# fCPU.net
KiCad netlist of a schematic drawn in EAGLE
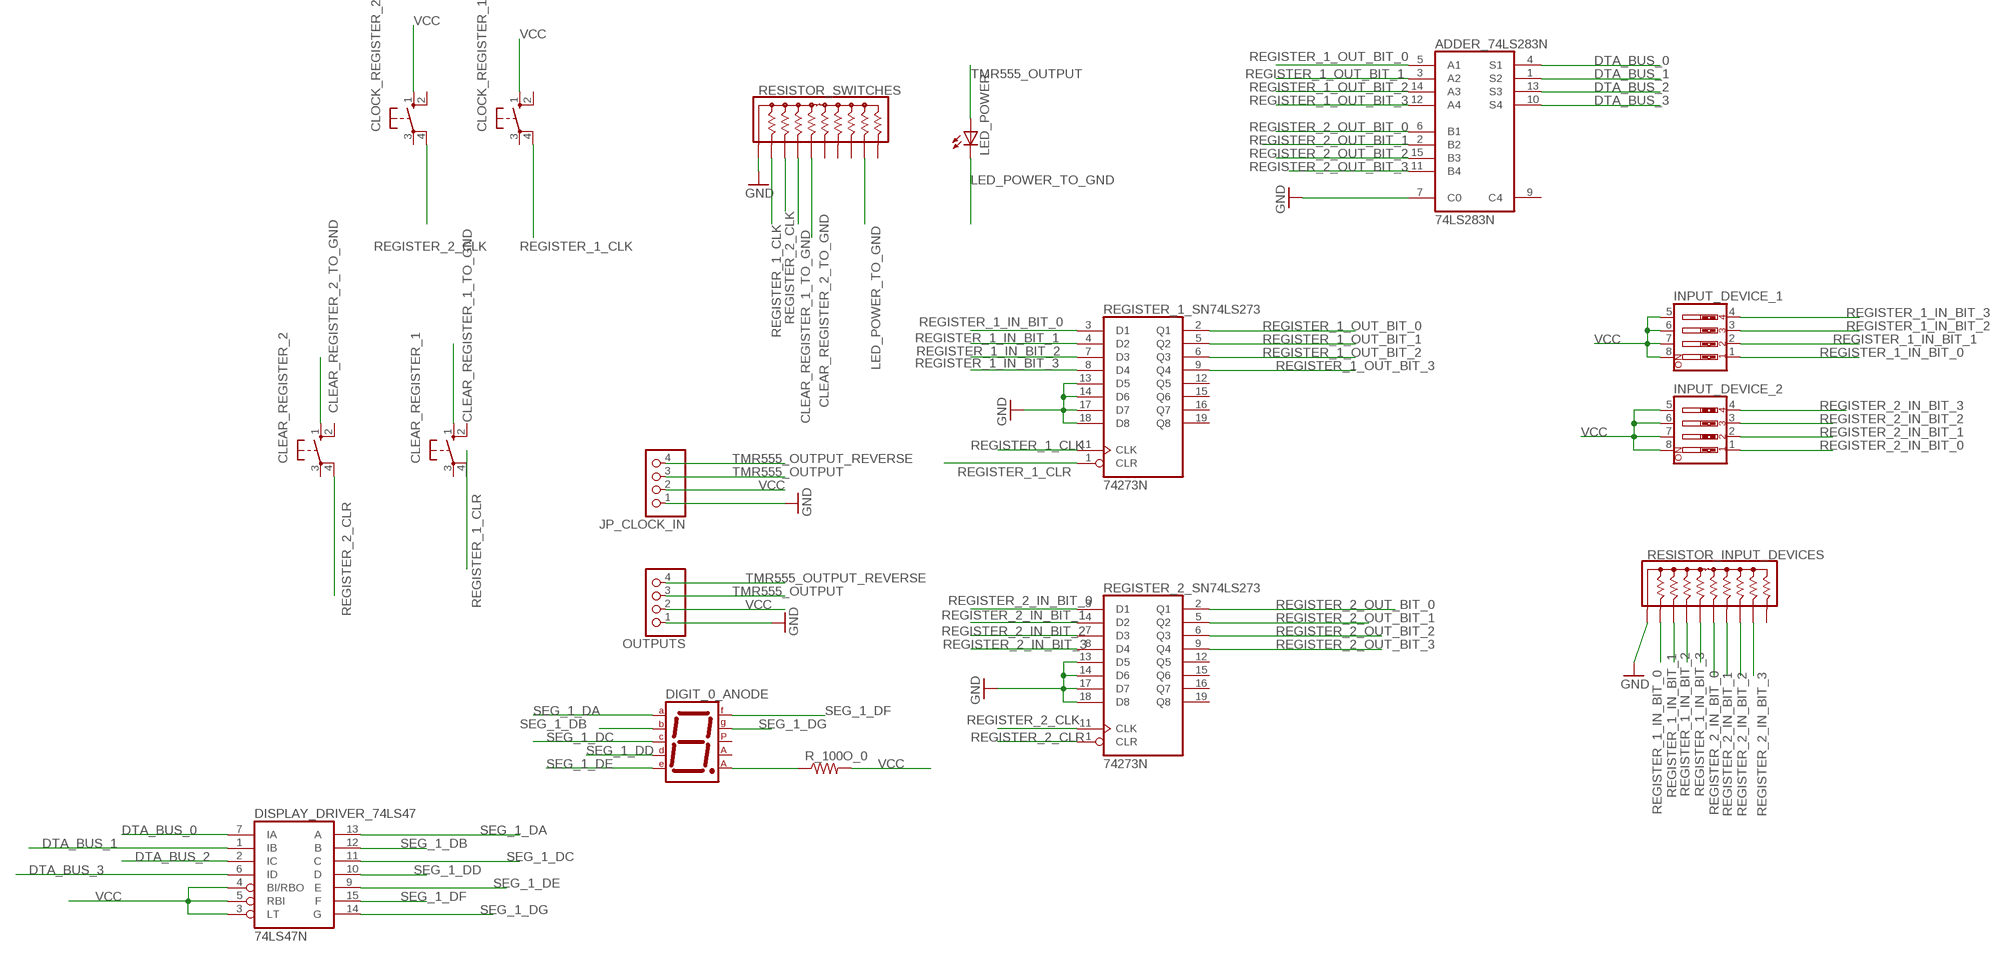
[diagram p0: schematic, sheet 1]

(export (version "E")
  (design (tool "Eeschema 10.0.6"))
  (components
    (comp (ref "ADDER_74LS283N")
      (value "74LS283N")
      (footprint "eagle-import:DIL16")
      (libsource (lib "eagle-import") (part "74283NLS"))
    )
    (comp (ref "CLEAR_REGISTER_1")
      (value "10-XX")
      (footprint "eagle-import:B3F-10XX")
      (fields (field (name "MPN") "B3F-1000"))
      (libsource (lib "eagle-import") (part "10-XX"))
    )
    (comp (ref "CLEAR_REGISTER_2")
      (value "10-XX")
      (footprint "eagle-import:B3F-10XX")
      (fields (field (name "MPN") "B3F-1000"))
      (libsource (lib "eagle-import") (part "10-XX"))
    )
    (comp (ref "CLOCK_REGISTER_1")
      (value "10-XX")
      (footprint "eagle-import:B3F-10XX")
      (fields (field (name "MPN") "B3F-1000"))
      (libsource (lib "eagle-import") (part "10-XX"))
    )
    (comp (ref "CLOCK_REGISTER_2")
      (value "10-XX")
      (footprint "eagle-import:B3F-10XX")
      (fields (field (name "MPN") "B3F-1000"))
      (libsource (lib "eagle-import") (part "10-XX"))
    )
    (comp (ref "DIGIT_0_ANODE")
      (value "7SEG-CA")
      (footprint "eagle-import:7SEG-13")
      (libsource (lib "eagle-import") (part "7SEG-CA"))
    )
    (comp (ref "DISPLAY_DRIVER_74LS47")
      (value "74LS47N")
      (footprint "eagle-import:DIL16")
      (libsource (lib "eagle-import") (part "7447NLS"))
    )
    (comp (ref "INPUT_DEVICE_1")
      (value "SW_DIP-4")
      (footprint "eagle-import:EDG-04")
      (libsource (lib "eagle-import") (part "SW_DIP-4"))
    )
    (comp (ref "INPUT_DEVICE_2")
      (value "SW_DIP-4")
      (footprint "eagle-import:EDG-04")
      (libsource (lib "eagle-import") (part "SW_DIP-4"))
    )
    (comp (ref "JP_CLOCK_IN")
      (value "PINHD-1X4")
      (footprint "eagle-import:1X04")
      (libsource (lib "eagle-import") (part "PINHD-1X4"))
    )
    (comp (ref "LED_POWER")
      (value "LEDSMT1206")
      (footprint "eagle-import:1206")
      (libsource (lib "eagle-import") (part "LEDSMT1206"))
    )
    (comp (ref "OUTPUTS")
      (value "PINHD-1X4")
      (footprint "eagle-import:1X04")
      (libsource (lib "eagle-import") (part "PINHD-1X4"))
    )
    (comp (ref "REGISTER_1_SN74LS273")
      (value "74273N")
      (footprint "eagle-import:DIL20")
      (libsource (lib "eagle-import") (part "74273N"))
    )
    (comp (ref "REGISTER_2_SN74LS273")
      (value "74273N")
      (footprint "eagle-import:DIL20")
      (libsource (lib "eagle-import") (part "74273N"))
    )
    (comp (ref "RESISTOR_INPUT_DEVICES")
      (value "4610X")
      (footprint "eagle-import:SIP10")
      (libsource (lib "eagle-import") (part "4610X"))
    )
    (comp (ref "RESISTOR_SWITCHES")
      (value "4610X")
      (footprint "eagle-import:SIP10")
      (libsource (lib "eagle-import") (part "4610X"))
    )
    (comp (ref "R_100O_0")
      (value "R-US_R1206")
      (footprint "eagle-import:R1206")
      (libsource (lib "eagle-import") (part "R-US_R1206"))
    )
  )
  (nets
    (net (code "1") (name "/CLEAR_REGISTER_1_TO_GND") (class "Default")
      (node (ref "CLEAR_REGISTER_1") (pin "1") (pinfunction "S_1") (pintype "passive"))
      (node (ref "RESISTOR_SWITCHES") (pin "4") (pinfunction "4_4") (pintype "passive"))
    )
    (net (code "2") (name "/CLEAR_REGISTER_2_TO_GND") (class "Default")
      (node (ref "CLEAR_REGISTER_2") (pin "1") (pinfunction "S_1") (pintype "passive"))
      (node (ref "RESISTOR_SWITCHES") (pin "5") (pinfunction "5_5") (pintype "passive"))
    )
    (net (code "3") (name "/DTA_BUS_0") (class "Default")
      (node (ref "ADDER_74LS283N") (pin "4") (pinfunction "S1_4") (pintype "output"))
      (node (ref "DISPLAY_DRIVER_74LS47") (pin "7") (pinfunction "IA_7") (pintype "input"))
    )
    (net (code "4") (name "/DTA_BUS_1") (class "Default")
      (node (ref "ADDER_74LS283N") (pin "1") (pinfunction "S2_1") (pintype "output"))
      (node (ref "DISPLAY_DRIVER_74LS47") (pin "1") (pinfunction "IB_1") (pintype "input"))
    )
    (net (code "5") (name "/DTA_BUS_2") (class "Default")
      (node (ref "ADDER_74LS283N") (pin "13") (pinfunction "S3_13") (pintype "output"))
      (node (ref "DISPLAY_DRIVER_74LS47") (pin "2") (pinfunction "IC_2") (pintype "input"))
    )
    (net (code "6") (name "/DTA_BUS_3") (class "Default")
      (node (ref "ADDER_74LS283N") (pin "10") (pinfunction "S4_10") (pintype "output"))
      (node (ref "DISPLAY_DRIVER_74LS47") (pin "6") (pinfunction "ID_6") (pintype "input"))
    )
    (net (code "7") (name "/LED_POWER_TO_GND") (class "Default")
      (node (ref "LED_POWER") (pin "C") (pinfunction "C_C") (pintype "passive"))
      (node (ref "RESISTOR_SWITCHES") (pin "9") (pinfunction "9_9") (pintype "passive"))
    )
    (net (code "8") (name "/REGISTER_1_CLK") (class "Default")
      (node (ref "CLOCK_REGISTER_1") (pin "4") (pinfunction "P1_4") (pintype "passive"))
      (node (ref "REGISTER_1_SN74LS273") (pin "11") (pinfunction "CLK_11") (pintype "input"))
      (node (ref "RESISTOR_SWITCHES") (pin "2") (pinfunction "2_2") (pintype "passive"))
    )
    (net (code "9") (name "/REGISTER_1_CLR") (class "Default")
      (node (ref "CLEAR_REGISTER_1") (pin "4") (pinfunction "P1_4") (pintype "passive"))
      (node (ref "REGISTER_1_SN74LS273") (pin "1") (pinfunction "CLR_1") (pintype "input"))
    )
    (net (code "10") (name "/REGISTER_1_IN_BIT_0") (class "Default")
      (node (ref "INPUT_DEVICE_1") (pin "1") (pinfunction "1_1") (pintype "passive"))
      (node (ref "REGISTER_1_SN74LS273") (pin "3") (pinfunction "D1_3") (pintype "input"))
      (node (ref "RESISTOR_INPUT_DEVICES") (pin "2") (pinfunction "2_2") (pintype "passive"))
    )
    (net (code "11") (name "/REGISTER_1_IN_BIT_1") (class "Default")
      (node (ref "INPUT_DEVICE_1") (pin "2") (pinfunction "2_2") (pintype "passive"))
      (node (ref "REGISTER_1_SN74LS273") (pin "4") (pinfunction "D2_4") (pintype "input"))
      (node (ref "RESISTOR_INPUT_DEVICES") (pin "3") (pinfunction "3_3") (pintype "passive"))
    )
    (net (code "12") (name "/REGISTER_1_IN_BIT_2") (class "Default")
      (node (ref "INPUT_DEVICE_1") (pin "3") (pinfunction "3_3") (pintype "passive"))
      (node (ref "REGISTER_1_SN74LS273") (pin "7") (pinfunction "D3_7") (pintype "input"))
      (node (ref "RESISTOR_INPUT_DEVICES") (pin "4") (pinfunction "4_4") (pintype "passive"))
    )
    (net (code "13") (name "/REGISTER_1_IN_BIT_3") (class "Default")
      (node (ref "INPUT_DEVICE_1") (pin "4") (pinfunction "4_4") (pintype "passive"))
      (node (ref "REGISTER_1_SN74LS273") (pin "8") (pinfunction "D4_8") (pintype "input"))
      (node (ref "RESISTOR_INPUT_DEVICES") (pin "5") (pinfunction "5_5") (pintype "passive"))
    )
    (net (code "14") (name "/REGISTER_1_OUT_BIT_0") (class "Default")
      (node (ref "ADDER_74LS283N") (pin "5") (pinfunction "A1_5") (pintype "input"))
      (node (ref "REGISTER_1_SN74LS273") (pin "2") (pinfunction "Q1_2") (pintype "output"))
    )
    (net (code "15") (name "/REGISTER_1_OUT_BIT_1") (class "Default")
      (node (ref "ADDER_74LS283N") (pin "3") (pinfunction "A2_3") (pintype "input"))
      (node (ref "REGISTER_1_SN74LS273") (pin "5") (pinfunction "Q2_5") (pintype "output"))
    )
    (net (code "16") (name "/REGISTER_1_OUT_BIT_2") (class "Default")
      (node (ref "ADDER_74LS283N") (pin "14") (pinfunction "A3_14") (pintype "input"))
      (node (ref "REGISTER_1_SN74LS273") (pin "6") (pinfunction "Q3_6") (pintype "output"))
    )
    (net (code "17") (name "/REGISTER_1_OUT_BIT_3") (class "Default")
      (node (ref "ADDER_74LS283N") (pin "12") (pinfunction "A4_12") (pintype "input"))
      (node (ref "REGISTER_1_SN74LS273") (pin "9") (pinfunction "Q4_9") (pintype "output"))
    )
    (net (code "18") (name "/REGISTER_2_CLK") (class "Default")
      (node (ref "CLOCK_REGISTER_2") (pin "4") (pinfunction "P1_4") (pintype "passive"))
      (node (ref "REGISTER_2_SN74LS273") (pin "11") (pinfunction "CLK_11") (pintype "input"))
      (node (ref "RESISTOR_SWITCHES") (pin "3") (pinfunction "3_3") (pintype "passive"))
    )
    (net (code "19") (name "/REGISTER_2_CLR") (class "Default")
      (node (ref "CLEAR_REGISTER_2") (pin "4") (pinfunction "P1_4") (pintype "passive"))
      (node (ref "REGISTER_2_SN74LS273") (pin "1") (pinfunction "CLR_1") (pintype "input"))
    )
    (net (code "20") (name "/REGISTER_2_IN_BIT_0") (class "Default")
      (node (ref "INPUT_DEVICE_2") (pin "1") (pinfunction "1_1") (pintype "passive"))
      (node (ref "REGISTER_2_SN74LS273") (pin "3") (pinfunction "D1_3") (pintype "input"))
      (node (ref "RESISTOR_INPUT_DEVICES") (pin "6") (pinfunction "6_6") (pintype "passive"))
    )
    (net (code "21") (name "/REGISTER_2_IN_BIT_1") (class "Default")
      (node (ref "INPUT_DEVICE_2") (pin "2") (pinfunction "2_2") (pintype "passive"))
      (node (ref "REGISTER_2_SN74LS273") (pin "4") (pinfunction "D2_4") (pintype "input"))
      (node (ref "RESISTOR_INPUT_DEVICES") (pin "7") (pinfunction "7_7") (pintype "passive"))
    )
    (net (code "22") (name "/REGISTER_2_IN_BIT_2") (class "Default")
      (node (ref "INPUT_DEVICE_2") (pin "3") (pinfunction "3_3") (pintype "passive"))
      (node (ref "REGISTER_2_SN74LS273") (pin "7") (pinfunction "D3_7") (pintype "input"))
      (node (ref "RESISTOR_INPUT_DEVICES") (pin "8") (pinfunction "8_8") (pintype "passive"))
    )
    (net (code "23") (name "/REGISTER_2_IN_BIT_3") (class "Default")
      (node (ref "INPUT_DEVICE_2") (pin "4") (pinfunction "4_4") (pintype "passive"))
      (node (ref "REGISTER_2_SN74LS273") (pin "8") (pinfunction "D4_8") (pintype "input"))
      (node (ref "RESISTOR_INPUT_DEVICES") (pin "9") (pinfunction "9_9") (pintype "passive"))
    )
    (net (code "24") (name "/REGISTER_2_OUT_BIT_0") (class "Default")
      (node (ref "ADDER_74LS283N") (pin "6") (pinfunction "B1_6") (pintype "input"))
      (node (ref "REGISTER_2_SN74LS273") (pin "2") (pinfunction "Q1_2") (pintype "output"))
    )
    (net (code "25") (name "/REGISTER_2_OUT_BIT_1") (class "Default")
      (node (ref "ADDER_74LS283N") (pin "2") (pinfunction "B2_2") (pintype "input"))
      (node (ref "REGISTER_2_SN74LS273") (pin "5") (pinfunction "Q2_5") (pintype "output"))
    )
    (net (code "26") (name "/REGISTER_2_OUT_BIT_2") (class "Default")
      (node (ref "ADDER_74LS283N") (pin "15") (pinfunction "B3_15") (pintype "input"))
      (node (ref "REGISTER_2_SN74LS273") (pin "6") (pinfunction "Q3_6") (pintype "output"))
    )
    (net (code "27") (name "/REGISTER_2_OUT_BIT_3") (class "Default")
      (node (ref "ADDER_74LS283N") (pin "11") (pinfunction "B4_11") (pintype "input"))
      (node (ref "REGISTER_2_SN74LS273") (pin "9") (pinfunction "Q4_9") (pintype "output"))
    )
    (net (code "28") (name "/SEG_1_DA") (class "Default")
      (node (ref "DIGIT_0_ANODE") (pin "7") (pinfunction "A_7") (pintype "passive"))
      (node (ref "DISPLAY_DRIVER_74LS47") (pin "13") (pinfunction "A_13") (pintype "output"))
    )
    (net (code "29") (name "/SEG_1_DB") (class "Default")
      (node (ref "DIGIT_0_ANODE") (pin "6") (pinfunction "B_6") (pintype "passive"))
      (node (ref "DISPLAY_DRIVER_74LS47") (pin "12") (pinfunction "B_12") (pintype "output"))
    )
    (net (code "30") (name "/SEG_1_DC") (class "Default")
      (node (ref "DIGIT_0_ANODE") (pin "4") (pinfunction "C_4") (pintype "passive"))
      (node (ref "DISPLAY_DRIVER_74LS47") (pin "11") (pinfunction "C_11") (pintype "output"))
    )
    (net (code "31") (name "/SEG_1_DD") (class "Default")
      (node (ref "DIGIT_0_ANODE") (pin "2") (pinfunction "D_2") (pintype "passive"))
      (node (ref "DISPLAY_DRIVER_74LS47") (pin "10") (pinfunction "D_10") (pintype "output"))
    )
    (net (code "32") (name "/SEG_1_DE") (class "Default")
      (node (ref "DIGIT_0_ANODE") (pin "1") (pinfunction "E_1") (pintype "passive"))
      (node (ref "DISPLAY_DRIVER_74LS47") (pin "9") (pinfunction "E_9") (pintype "output"))
    )
    (net (code "33") (name "/SEG_1_DF") (class "Default")
      (node (ref "DIGIT_0_ANODE") (pin "9") (pinfunction "F_9") (pintype "passive"))
      (node (ref "DISPLAY_DRIVER_74LS47") (pin "15") (pinfunction "F_15") (pintype "output"))
    )
    (net (code "34") (name "/SEG_1_DG") (class "Default")
      (node (ref "DIGIT_0_ANODE") (pin "10") (pinfunction "G_10") (pintype "passive"))
      (node (ref "DISPLAY_DRIVER_74LS47") (pin "14") (pinfunction "G_14") (pintype "output"))
    )
    (net (code "35") (name "/TMR555_OUTPUT") (class "Default")
      (node (ref "JP_CLOCK_IN") (pin "3") (pinfunction "3_3") (pintype "passive"))
      (node (ref "LED_POWER") (pin "A") (pinfunction "A_A") (pintype "passive"))
      (node (ref "OUTPUTS") (pin "3") (pinfunction "3_3") (pintype "passive"))
    )
    (net (code "36") (name "/TMR555_OUTPUT_REVERSE") (class "Default")
      (node (ref "JP_CLOCK_IN") (pin "4") (pinfunction "4_4") (pintype "passive"))
      (node (ref "OUTPUTS") (pin "4") (pinfunction "4_4") (pintype "passive"))
    )
    (net (code "37") (name "/VCC") (class "Default")
      (node (ref "CLOCK_REGISTER_1") (pin "1") (pinfunction "S_1") (pintype "passive"))
      (node (ref "CLOCK_REGISTER_2") (pin "1") (pinfunction "S_1") (pintype "passive"))
      (node (ref "DISPLAY_DRIVER_74LS47") (pin "3") (pinfunction "LT_3") (pintype "input"))
      (node (ref "DISPLAY_DRIVER_74LS47") (pin "4") (pinfunction "BI/RBO_4") (pintype "input"))
      (node (ref "DISPLAY_DRIVER_74LS47") (pin "5") (pinfunction "RBI_5") (pintype "input"))
      (node (ref "INPUT_DEVICE_1") (pin "5") (pinfunction "5_5") (pintype "passive"))
      (node (ref "INPUT_DEVICE_1") (pin "6") (pinfunction "6_6") (pintype "passive"))
      (node (ref "INPUT_DEVICE_1") (pin "7") (pinfunction "7_7") (pintype "passive"))
      (node (ref "INPUT_DEVICE_1") (pin "8") (pinfunction "8_8") (pintype "passive"))
      (node (ref "INPUT_DEVICE_2") (pin "5") (pinfunction "5_5") (pintype "passive"))
      (node (ref "INPUT_DEVICE_2") (pin "6") (pinfunction "6_6") (pintype "passive"))
      (node (ref "INPUT_DEVICE_2") (pin "7") (pinfunction "7_7") (pintype "passive"))
      (node (ref "INPUT_DEVICE_2") (pin "8") (pinfunction "8_8") (pintype "passive"))
      (node (ref "JP_CLOCK_IN") (pin "2") (pinfunction "2_2") (pintype "passive"))
      (node (ref "OUTPUTS") (pin "2") (pinfunction "2_2") (pintype "passive"))
      (node (ref "R_100O_0") (pin "2") (pinfunction "2_2") (pintype "passive"))
    )
    (net (code "38") (name "GND") (class "Default")
      (node (ref "ADDER_74LS283N") (pin "7") (pinfunction "C0_7") (pintype "input"))
      (node (ref "JP_CLOCK_IN") (pin "1") (pinfunction "1_1") (pintype "passive"))
      (node (ref "OUTPUTS") (pin "1") (pinfunction "1_1") (pintype "passive"))
      (node (ref "REGISTER_1_SN74LS273") (pin "13") (pinfunction "D5_13") (pintype "input"))
      (node (ref "REGISTER_1_SN74LS273") (pin "14") (pinfunction "D6_14") (pintype "input"))
      (node (ref "REGISTER_1_SN74LS273") (pin "17") (pinfunction "D7_17") (pintype "input"))
      (node (ref "REGISTER_1_SN74LS273") (pin "18") (pinfunction "D8_18") (pintype "input"))
      (node (ref "REGISTER_2_SN74LS273") (pin "13") (pinfunction "D5_13") (pintype "input"))
      (node (ref "REGISTER_2_SN74LS273") (pin "14") (pinfunction "D6_14") (pintype "input"))
      (node (ref "REGISTER_2_SN74LS273") (pin "17") (pinfunction "D7_17") (pintype "input"))
      (node (ref "REGISTER_2_SN74LS273") (pin "18") (pinfunction "D8_18") (pintype "input"))
      (node (ref "RESISTOR_INPUT_DEVICES") (pin "1") (pinfunction "1_1") (pintype "passive"))
      (node (ref "RESISTOR_SWITCHES") (pin "1") (pinfunction "1_1") (pintype "passive"))
    )
    (net (code "39") (name "Net-(DIGIT_0_ANODE-CA2)") (class "Default")
      (node (ref "DIGIT_0_ANODE") (pin "8") (pinfunction "CA2_8") (pintype "passive"))
      (node (ref "R_100O_0") (pin "1") (pinfunction "1_1") (pintype "passive"))
    )
    (net (code "40") (name "unconnected-(ADDER_74LS283NA-C4-Pad9)") (class "Default")
      (node (ref "ADDER_74LS283N") (pin "9") (pinfunction "C4_9") (pintype "output"))
    )
    (net (code "41") (name "unconnected-(CLEAR_REGISTER_1-P-Pad3)") (class "Default")
      (node (ref "CLEAR_REGISTER_1") (pin "3") (pinfunction "P_3") (pintype "passive"))
    )
    (net (code "42") (name "unconnected-(CLEAR_REGISTER_1-S1-Pad2)") (class "Default")
      (node (ref "CLEAR_REGISTER_1") (pin "2") (pinfunction "S1_2") (pintype "passive"))
    )
    (net (code "43") (name "unconnected-(CLEAR_REGISTER_2-P-Pad3)") (class "Default")
      (node (ref "CLEAR_REGISTER_2") (pin "3") (pinfunction "P_3") (pintype "passive"))
    )
    (net (code "44") (name "unconnected-(CLEAR_REGISTER_2-S1-Pad2)") (class "Default")
      (node (ref "CLEAR_REGISTER_2") (pin "2") (pinfunction "S1_2") (pintype "passive"))
    )
    (net (code "45") (name "unconnected-(CLOCK_REGISTER_1-P-Pad3)") (class "Default")
      (node (ref "CLOCK_REGISTER_1") (pin "3") (pinfunction "P_3") (pintype "passive"))
    )
    (net (code "46") (name "unconnected-(CLOCK_REGISTER_1-S1-Pad2)") (class "Default")
      (node (ref "CLOCK_REGISTER_1") (pin "2") (pinfunction "S1_2") (pintype "passive"))
    )
    (net (code "47") (name "unconnected-(CLOCK_REGISTER_2-P-Pad3)") (class "Default")
      (node (ref "CLOCK_REGISTER_2") (pin "3") (pinfunction "P_3") (pintype "passive"))
    )
    (net (code "48") (name "unconnected-(CLOCK_REGISTER_2-S1-Pad2)") (class "Default")
      (node (ref "CLOCK_REGISTER_2") (pin "2") (pinfunction "S1_2") (pintype "passive"))
    )
    (net (code "49") (name "unconnected-(DIGIT_0_ANODE-CA1-Pad3)") (class "Default")
      (node (ref "DIGIT_0_ANODE") (pin "3") (pinfunction "CA1_3") (pintype "passive"))
    )
    (net (code "50") (name "unconnected-(DIGIT_0_ANODE-DP-Pad5)") (class "Default")
      (node (ref "DIGIT_0_ANODE") (pin "5") (pinfunction "DP_5") (pintype "passive"))
    )
    (net (code "51") (name "unconnected-(REGISTER_1_SN74LS273A-Q5-Pad12)") (class "Default")
      (node (ref "REGISTER_1_SN74LS273") (pin "12") (pinfunction "Q5_12") (pintype "output"))
    )
    (net (code "52") (name "unconnected-(REGISTER_1_SN74LS273A-Q6-Pad15)") (class "Default")
      (node (ref "REGISTER_1_SN74LS273") (pin "15") (pinfunction "Q6_15") (pintype "output"))
    )
    (net (code "53") (name "unconnected-(REGISTER_1_SN74LS273A-Q7-Pad16)") (class "Default")
      (node (ref "REGISTER_1_SN74LS273") (pin "16") (pinfunction "Q7_16") (pintype "output"))
    )
    (net (code "54") (name "unconnected-(REGISTER_1_SN74LS273A-Q8-Pad19)") (class "Default")
      (node (ref "REGISTER_1_SN74LS273") (pin "19") (pinfunction "Q8_19") (pintype "output"))
    )
    (net (code "55") (name "unconnected-(REGISTER_2_SN74LS273A-Q5-Pad12)") (class "Default")
      (node (ref "REGISTER_2_SN74LS273") (pin "12") (pinfunction "Q5_12") (pintype "output"))
    )
    (net (code "56") (name "unconnected-(REGISTER_2_SN74LS273A-Q6-Pad15)") (class "Default")
      (node (ref "REGISTER_2_SN74LS273") (pin "15") (pinfunction "Q6_15") (pintype "output"))
    )
    (net (code "57") (name "unconnected-(REGISTER_2_SN74LS273A-Q7-Pad16)") (class "Default")
      (node (ref "REGISTER_2_SN74LS273") (pin "16") (pinfunction "Q7_16") (pintype "output"))
    )
    (net (code "58") (name "unconnected-(REGISTER_2_SN74LS273A-Q8-Pad19)") (class "Default")
      (node (ref "REGISTER_2_SN74LS273") (pin "19") (pinfunction "Q8_19") (pintype "output"))
    )
    (net (code "59") (name "unconnected-(RESISTOR_INPUT_DEVICES-Pad10)") (class "Default")
      (node (ref "RESISTOR_INPUT_DEVICES") (pin "10") (pinfunction "10_10") (pintype "passive"))
    )
    (net (code "60") (name "unconnected-(RESISTOR_SWITCHES-Pad6)") (class "Default")
      (node (ref "RESISTOR_SWITCHES") (pin "6") (pinfunction "6_6") (pintype "passive"))
    )
    (net (code "61") (name "unconnected-(RESISTOR_SWITCHES-Pad7)") (class "Default")
      (node (ref "RESISTOR_SWITCHES") (pin "7") (pinfunction "7_7") (pintype "passive"))
    )
    (net (code "62") (name "unconnected-(RESISTOR_SWITCHES-Pad8)") (class "Default")
      (node (ref "RESISTOR_SWITCHES") (pin "8") (pinfunction "8_8") (pintype "passive"))
    )
    (net (code "63") (name "unconnected-(RESISTOR_SWITCHES-Pad10)") (class "Default")
      (node (ref "RESISTOR_SWITCHES") (pin "10") (pinfunction "10_10") (pintype "passive"))
    )
  )
)
